# FlukeNic_UNITA.net
KiCad netlist of a schematic drawn in EAGLE
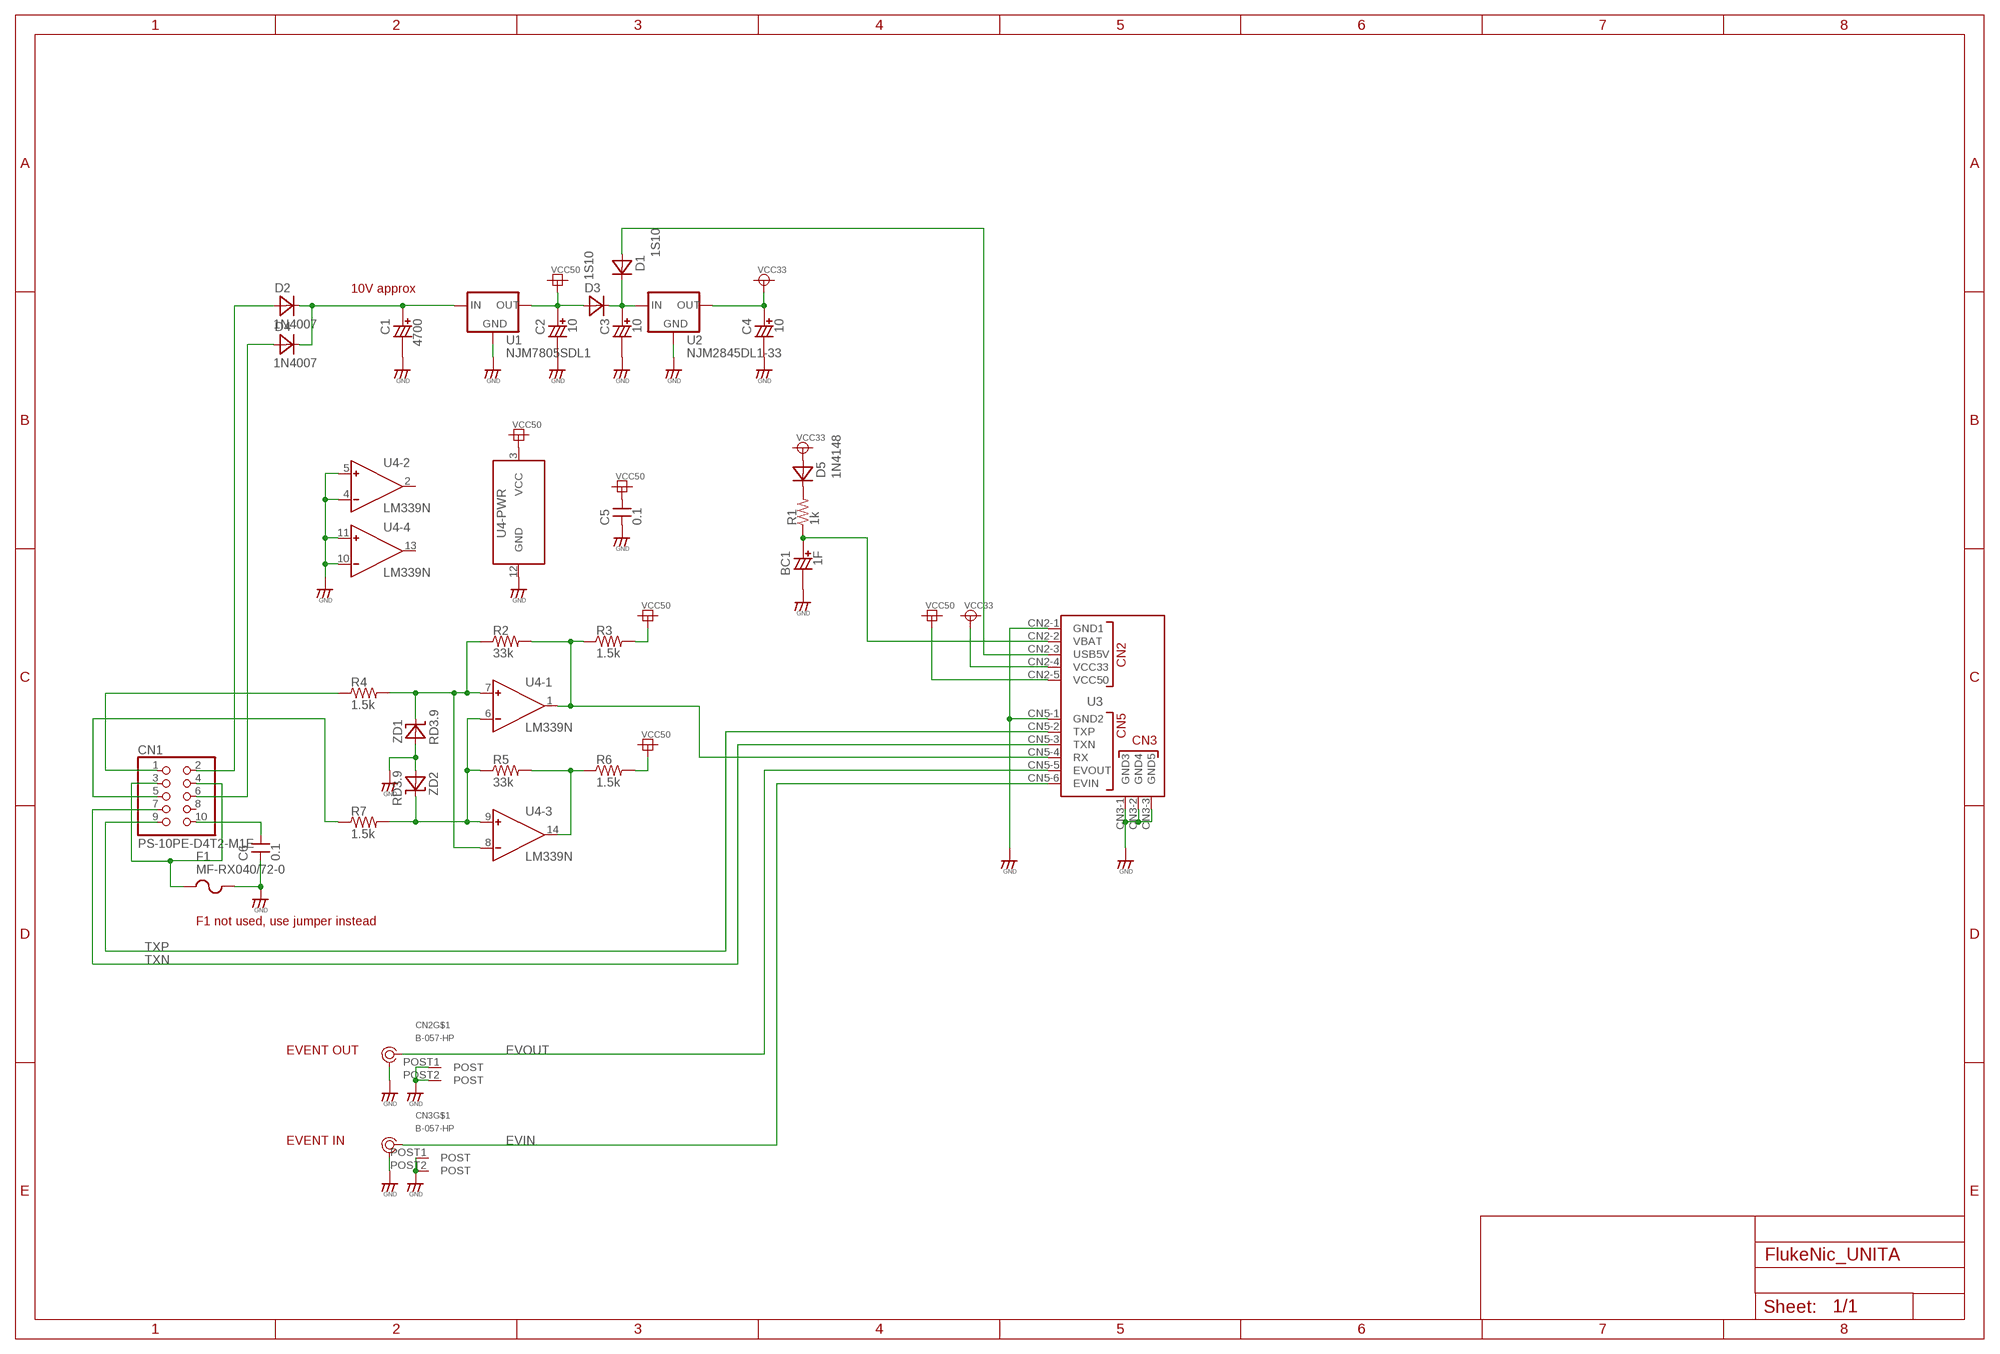
[diagram p0: schematic, sheet 1]

(export (version "E")
  (design (tool "Eeschema 10.0.6"))
  (components
    (comp (ref "BC1")
      (value "1F")
      (footprint "eagle-import:SE-5R5-D105VY")
      (libsource (lib "eagle-import") (part "EDLCSE-5R5-D105VY"))
    )
    (comp (ref "C1")
      (value "4700")
      (footprint "eagle-import:CCAP_16")
      (libsource (lib "eagle-import") (part "CCAP16"))
    )
    (comp (ref "C2")
      (value "10")
      (footprint "eagle-import:CCAP_6.5")
      (libsource (lib "eagle-import") (part "CCAP6.5"))
    )
    (comp (ref "C3")
      (value "10")
      (footprint "eagle-import:CCAP_6.5")
      (libsource (lib "eagle-import") (part "CCAP6.5"))
    )
    (comp (ref "C4")
      (value "10")
      (footprint "eagle-import:CCAP_6.5")
      (libsource (lib "eagle-import") (part "CCAP6.5"))
    )
    (comp (ref "C5")
      (value "0.1")
      (footprint "eagle-import:CAP_DIP_2")
      (libsource (lib "eagle-import") (part "CAPDIP_2"))
    )
    (comp (ref "C6")
      (value "0.1")
      (footprint "eagle-import:CAP_DIP_2")
      (libsource (lib "eagle-import") (part "CAPDIP_2"))
    )
    (comp (ref "CN1")
      (value "PS-10PE-D4T2-M1E")
      (footprint "eagle-import:PS-10PE-D4T2-M1E")
      (libsource (lib "eagle-import") (part "PS-10PE-D4T2-M1E"))
    )
    (comp (ref "CN2")
      (value "B-057-HP")
      (footprint "eagle-import:B-057-HP")
      (libsource (lib "eagle-import") (part "B-057-HP"))
    )
    (comp (ref "CN3")
      (value "B-057-HP")
      (footprint "eagle-import:B-057-HP")
      (libsource (lib "eagle-import") (part "B-057-HP"))
    )
    (comp (ref "D1")
      (value "1S10")
      (footprint "eagle-import:DIODE_4_1MM")
      (libsource (lib "eagle-import") (part "DIODEGENERIC_4_1MM"))
    )
    (comp (ref "D2")
      (value "1N4007")
      (footprint "eagle-import:DIODE_4_1MM")
      (libsource (lib "eagle-import") (part "DIODEGENERIC_4_1MM"))
    )
    (comp (ref "D3")
      (value "1S10")
      (footprint "eagle-import:DIODE_4_1MM")
      (libsource (lib "eagle-import") (part "DIODEGENERIC_4_1MM"))
    )
    (comp (ref "D4")
      (value "1N4007")
      (footprint "eagle-import:DIODE_4_1MM")
      (libsource (lib "eagle-import") (part "DIODEGENERIC_4_1MM"))
    )
    (comp (ref "D5")
      (value "1N4148")
      (footprint "eagle-import:DIODE_4")
      (libsource (lib "eagle-import") (part "DIODEGENERIC_4"))
    )
    (comp (ref "F1")
      (value "MF-RX040/72-0")
      (footprint "eagle-import:AX_08X02_2P_200")
      (libsource (lib "eagle-import") (part "POLYSW8X2MM"))
    )
    (comp (ref "R1")
      (value "1k")
      (footprint "eagle-import:R_0.25W_4")
      (libsource (lib "eagle-import") (part "R0.25W_4P"))
    )
    (comp (ref "R2")
      (value "33k")
      (footprint "eagle-import:R_0.25W_4")
      (libsource (lib "eagle-import") (part "R0.25W_4P"))
    )
    (comp (ref "R3")
      (value "1.5k")
      (footprint "eagle-import:R_0.25W_4")
      (libsource (lib "eagle-import") (part "R0.25W_4P"))
    )
    (comp (ref "R4")
      (value "1.5k")
      (footprint "eagle-import:R_0.25W_4")
      (libsource (lib "eagle-import") (part "R0.25W_4P"))
    )
    (comp (ref "R5")
      (value "33k")
      (footprint "eagle-import:R_0.25W_4")
      (libsource (lib "eagle-import") (part "R0.25W_4P"))
    )
    (comp (ref "R6")
      (value "1.5k")
      (footprint "eagle-import:R_0.25W_4")
      (libsource (lib "eagle-import") (part "R0.25W_4P"))
    )
    (comp (ref "R7")
      (value "1.5k")
      (footprint "eagle-import:R_0.25W_4")
      (libsource (lib "eagle-import") (part "R0.25W_4P"))
    )
    (comp (ref "U1")
      (value "NJM7805SDL1")
      (footprint "eagle-import:TO252")
      (libsource (lib "eagle-import") (part "78XXTO252"))
    )
    (comp (ref "U2")
      (value "NJM2845DL1-33")
      (footprint "eagle-import:TO252")
      (libsource (lib "eagle-import") (part "NJM2845"))
    )
    (comp (ref "U3")
      (value "UNITB")
      (footprint "eagle-import:UNITB")
      (libsource (lib "eagle-import") (part "UNITB"))
    )
    (comp (ref "U4")
      (value "LM339N")
      (footprint "eagle-import:DIL14")
      (libsource (lib "eagle-import") (part "LM339N"))
    )
    (comp (ref "ZD1")
      (value "RD3.9")
      (footprint "eagle-import:DIODE_4")
      (libsource (lib "eagle-import") (part "ZENER_DIODE4"))
    )
    (comp (ref "ZD2")
      (value "RD3.9")
      (footprint "eagle-import:DIODE_4")
      (libsource (lib "eagle-import") (part "ZENER_DIODE4"))
    )
  )
  (nets
    (net (code "1") (name "/EVIN") (class "Default")
      (node (ref "CN3") (pin "HOT") (pinfunction "HOT_HOT") (pintype "passive"))
      (node (ref "U3") (pin "CN5-6") (pinfunction "EVIN_CN5-6") (pintype "input"))
    )
    (net (code "2") (name "/EVOUT") (class "Default")
      (node (ref "CN2") (pin "HOT") (pinfunction "HOT_HOT") (pintype "passive"))
      (node (ref "U3") (pin "CN5-5") (pinfunction "EVOUT_CN5-5") (pintype "output"))
    )
    (net (code "3") (name "/TXN") (class "Default")
      (node (ref "CN1") (pin "7") (pinfunction "7_7") (pintype "passive"))
      (node (ref "U3") (pin "CN5-3") (pinfunction "TXN_CN5-3") (pintype "output"))
    )
    (net (code "4") (name "/TXP") (class "Default")
      (node (ref "CN1") (pin "9") (pinfunction "9_9") (pintype "passive"))
      (node (ref "U3") (pin "CN5-2") (pinfunction "TXP_CN5-2") (pintype "output"))
    )
    (net (code "5") (name "GND") (class "Default")
      (node (ref "BC1") (pin "-") (pinfunction "-_-") (pintype "passive"))
      (node (ref "C1") (pin "-") (pinfunction "-_-") (pintype "passive"))
      (node (ref "C2") (pin "-") (pinfunction "-_-") (pintype "passive"))
      (node (ref "C3") (pin "-") (pinfunction "-_-") (pintype "passive"))
      (node (ref "C4") (pin "-") (pinfunction "-_-") (pintype "passive"))
      (node (ref "C5") (pin "1") (pinfunction "1_1") (pintype "passive"))
      (node (ref "C6") (pin "1") (pinfunction "1_1") (pintype "passive"))
      (node (ref "CN2") (pin "COLD") (pinfunction "COLD_COLD") (pintype "passive"))
      (node (ref "CN2") (pin "POST1") (pinfunction "POST_POST1") (pintype "passive"))
      (node (ref "CN2") (pin "POST2") (pinfunction "POST_POST2") (pintype "passive"))
      (node (ref "CN3") (pin "COLD") (pinfunction "COLD_COLD") (pintype "passive"))
      (node (ref "CN3") (pin "POST1") (pinfunction "POST_POST1") (pintype "passive"))
      (node (ref "CN3") (pin "POST2") (pinfunction "POST_POST2") (pintype "passive"))
      (node (ref "F1") (pin "2") (pinfunction "P$2_2") (pintype "passive"))
      (node (ref "U1") (pin "2") (pinfunction "GND_2") (pintype "input"))
      (node (ref "U2") (pin "2") (pinfunction "GND_2") (pintype "input"))
      (node (ref "U3") (pin "CN2-1") (pinfunction "GND1_CN2-1") (pintype "power_in"))
      (node (ref "U3") (pin "CN3-1") (pinfunction "GND3_CN3-1") (pintype "power_in"))
      (node (ref "U3") (pin "CN3-2") (pinfunction "GND4_CN3-2") (pintype "power_in"))
      (node (ref "U3") (pin "CN3-3") (pinfunction "GND5_CN3-3") (pintype "power_in"))
      (node (ref "U3") (pin "CN5-1") (pinfunction "GND2_CN5-1") (pintype "power_in"))
      (node (ref "U4") (pin "10") (pinfunction "IN-_10") (pintype "input"))
      (node (ref "U4") (pin "11") (pinfunction "IN+_11") (pintype "input"))
      (node (ref "U4") (pin "12") (pinfunction "GND_12") (pintype "power_in"))
      (node (ref "U4") (pin "4") (pinfunction "IN-_4") (pintype "input"))
      (node (ref "U4") (pin "5") (pinfunction "IN+_5") (pintype "input"))
      (node (ref "ZD1") (pin "A") (pinfunction "A_A") (pintype "passive"))
      (node (ref "ZD2") (pin "A") (pinfunction "A_A") (pintype "passive"))
    )
    (net (code "6") (name "Net-(C6-Pad2)") (class "Default")
      (node (ref "C6") (pin "2") (pinfunction "2_2") (pintype "passive"))
      (node (ref "CN1") (pin "10") (pinfunction "10_10") (pintype "passive"))
    )
    (net (code "7") (name "Net-(CN1-Pad1)") (class "Default")
      (node (ref "CN1") (pin "1") (pinfunction "1_1") (pintype "passive"))
      (node (ref "R4") (pin "1") (pinfunction "1_1") (pintype "passive"))
    )
    (net (code "8") (name "Net-(CN1-Pad2)") (class "Default")
      (node (ref "CN1") (pin "2") (pinfunction "2_2") (pintype "passive"))
      (node (ref "D2") (pin "A") (pinfunction "A_A") (pintype "passive"))
    )
    (net (code "9") (name "Net-(CN1-Pad5)") (class "Default")
      (node (ref "CN1") (pin "5") (pinfunction "5_5") (pintype "passive"))
      (node (ref "R7") (pin "1") (pinfunction "1_1") (pintype "passive"))
    )
    (net (code "10") (name "Net-(CN1-Pad6)") (class "Default")
      (node (ref "CN1") (pin "6") (pinfunction "6_6") (pintype "passive"))
      (node (ref "D4") (pin "A") (pinfunction "A_A") (pintype "passive"))
    )
    (net (code "11") (name "Net-(D5-PadK)") (class "Default")
      (node (ref "D5") (pin "K") (pinfunction "K_K") (pintype "passive"))
      (node (ref "R1") (pin "2") (pinfunction "2_2") (pintype "passive"))
    )
    (net (code "12") (name "Net-(F1-P$1)") (class "Default")
      (node (ref "CN1") (pin "3") (pinfunction "3_3") (pintype "passive"))
      (node (ref "CN1") (pin "4") (pinfunction "4_4") (pintype "passive"))
      (node (ref "F1") (pin "1") (pinfunction "P$1_1") (pintype "passive"))
    )
    (net (code "13") (name "Net-(U1-IN)") (class "Default")
      (node (ref "C1") (pin "+") (pinfunction "+_+") (pintype "passive"))
      (node (ref "D2") (pin "K") (pinfunction "K_K") (pintype "passive"))
      (node (ref "D4") (pin "K") (pinfunction "K_K") (pintype "passive"))
      (node (ref "U1") (pin "1") (pinfunction "IN_1") (pintype "input"))
    )
    (net (code "14") (name "Net-(U2-IN)") (class "Default")
      (node (ref "C3") (pin "+") (pinfunction "+_+") (pintype "passive"))
      (node (ref "D1") (pin "K") (pinfunction "K_K") (pintype "passive"))
      (node (ref "D3") (pin "K") (pinfunction "K_K") (pintype "passive"))
      (node (ref "U2") (pin "1") (pinfunction "IN_1") (pintype "input"))
    )
    (net (code "15") (name "Net-(U3-RX)") (class "Default")
      (node (ref "R2") (pin "2") (pinfunction "2_2") (pintype "passive"))
      (node (ref "R3") (pin "1") (pinfunction "1_1") (pintype "passive"))
      (node (ref "U3") (pin "CN5-4") (pinfunction "RX_CN5-4") (pintype "input"))
      (node (ref "U4") (pin "1") (pinfunction "OUT_1") (pintype "output"))
    )
    (net (code "16") (name "Net-(U3-USB5V)") (class "Default")
      (node (ref "D1") (pin "A") (pinfunction "A_A") (pintype "passive"))
      (node (ref "U3") (pin "CN2-3") (pinfunction "USB5V_CN2-3") (pintype "power_in"))
    )
    (net (code "17") (name "Net-(U3-VBAT)") (class "Default")
      (node (ref "BC1") (pin "+") (pinfunction "+_+") (pintype "passive"))
      (node (ref "R1") (pin "1") (pinfunction "1_1") (pintype "passive"))
      (node (ref "U3") (pin "CN2-2") (pinfunction "VBAT_CN2-2") (pintype "power_in"))
    )
    (net (code "18") (name "Net-(U4A-IN+)") (class "Default")
      (node (ref "R2") (pin "1") (pinfunction "1_1") (pintype "passive"))
      (node (ref "R4") (pin "2") (pinfunction "2_2") (pintype "passive"))
      (node (ref "U4") (pin "7") (pinfunction "IN+_7") (pintype "input"))
      (node (ref "U4") (pin "8") (pinfunction "IN-_8") (pintype "input"))
      (node (ref "ZD1") (pin "K") (pinfunction "K_K") (pintype "passive"))
    )
    (net (code "19") (name "Net-(U4A-IN-)") (class "Default")
      (node (ref "R5") (pin "1") (pinfunction "1_1") (pintype "passive"))
      (node (ref "R7") (pin "2") (pinfunction "2_2") (pintype "passive"))
      (node (ref "U4") (pin "6") (pinfunction "IN-_6") (pintype "input"))
      (node (ref "U4") (pin "9") (pinfunction "IN+_9") (pintype "input"))
      (node (ref "ZD2") (pin "K") (pinfunction "K_K") (pintype "passive"))
    )
    (net (code "20") (name "Net-(U4C-OUT)") (class "Default")
      (node (ref "R5") (pin "2") (pinfunction "2_2") (pintype "passive"))
      (node (ref "R6") (pin "1") (pinfunction "1_1") (pintype "passive"))
      (node (ref "U4") (pin "14") (pinfunction "OUT_14") (pintype "output"))
    )
    (net (code "21") (name "VCC33") (class "Default")
      (node (ref "C4") (pin "+") (pinfunction "+_+") (pintype "passive"))
      (node (ref "D5") (pin "A") (pinfunction "A_A") (pintype "passive"))
      (node (ref "U2") (pin "3") (pinfunction "OUT_3") (pintype "passive"))
      (node (ref "U3") (pin "CN2-4") (pinfunction "VCC33_CN2-4") (pintype "power_in"))
    )
    (net (code "22") (name "VCC50") (class "Default")
      (node (ref "C2") (pin "+") (pinfunction "+_+") (pintype "passive"))
      (node (ref "C5") (pin "2") (pinfunction "2_2") (pintype "passive"))
      (node (ref "D3") (pin "A") (pinfunction "A_A") (pintype "passive"))
      (node (ref "R3") (pin "2") (pinfunction "2_2") (pintype "passive"))
      (node (ref "R6") (pin "2") (pinfunction "2_2") (pintype "passive"))
      (node (ref "U1") (pin "3") (pinfunction "OUT_3") (pintype "passive"))
      (node (ref "U3") (pin "CN2-5") (pinfunction "VCC50_CN2-5") (pintype "power_in"))
      (node (ref "U4") (pin "3") (pinfunction "VCC_3") (pintype "power_in"))
    )
    (net (code "23") (name "unconnected-(CN1-Pad8)") (class "Default")
      (node (ref "CN1") (pin "8") (pinfunction "8_8") (pintype "passive"))
    )
    (net (code "24") (name "unconnected-(U4B-OUT-Pad2)") (class "Default")
      (node (ref "U4") (pin "2") (pinfunction "OUT_2") (pintype "output"))
    )
    (net (code "25") (name "unconnected-(U4D-OUT-Pad13)") (class "Default")
      (node (ref "U4") (pin "13") (pinfunction "OUT_13") (pintype "output"))
    )
  )
)
